# Driver-v1.net
KiCad netlist of a schematic drawn in EAGLE
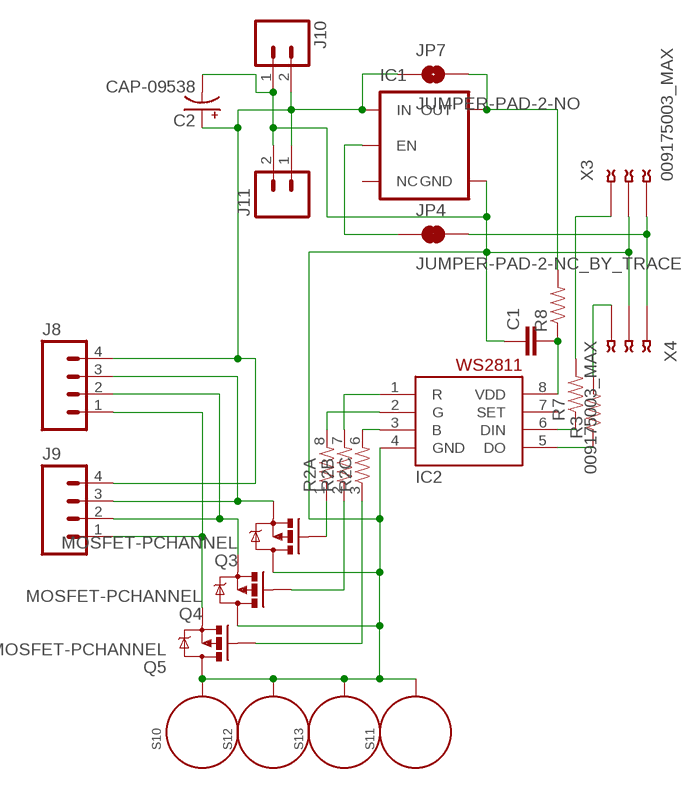
[diagram p0: schematic, sheet 1]

(export (version "E")
  (design (tool "Eeschema 10.0.6"))
  (components
    (comp (ref "C1")
      (value "CAP1206")
      (footprint "eagle-import:1206")
      (libsource (lib "eagle-import") (part "CAP1206"))
    )
    (comp (ref "C2")
      (value "CAP-09538")
      (footprint "eagle-import:CPOL-RADIAL-1000UF-25V")
      (libsource (lib "eagle-import") (part "1000UF-25V(PTH)"))
    )
    (comp (ref "IC1")
      (value "V_REG_TPS76433SOT23-5")
      (footprint "eagle-import:SOT23-5")
      (libsource (lib "eagle-import") (part "V_REG_TPS76433SOT23-5"))
    )
    (comp (ref "IC2")
      (value "WS2811-SOP8")
      (footprint "eagle-import:SO08-SKINNYPADS")
      (libsource (lib "eagle-import") (part "WS2811-SOP8"))
    )
    (comp (ref "J8")
      (value "M04LONGPADS")
      (footprint "eagle-import:1X04_LONGPADS")
      (libsource (lib "eagle-import") (part "M04LONGPADS"))
    )
    (comp (ref "J9")
      (value "M04LONGPADS")
      (footprint "eagle-import:1X04_LONGPADS")
      (libsource (lib "eagle-import") (part "M04LONGPADS"))
    )
    (comp (ref "J10")
      (value "M025MM")
      (footprint "eagle-import:SCREWTERMINAL-5MM-2")
      (libsource (lib "eagle-import") (part "M025MM"))
    )
    (comp (ref "J11")
      (value "M025MM")
      (footprint "eagle-import:SCREWTERMINAL-5MM-2")
      (libsource (lib "eagle-import") (part "M025MM"))
    )
    (comp (ref "JP4")
      (value "JUMPER-PAD-2-NC_BY_TRACE")
      (footprint "eagle-import:PAD-JUMPER-2-NC_BY_TRACE_YES_SILK")
      (libsource (lib "eagle-import") (part "JUMPER-PAD-2-NC_BY_TRACE"))
    )
    (comp (ref "JP7")
      (value "JUMPER-PAD-2-NO")
      (footprint "eagle-import:PAD-JUMPER-2-NO_NO_SILK")
      (libsource (lib "eagle-import") (part "JUMPER-PAD-2-NO"))
    )
    (comp (ref "Q3")
      (value "MOSFET-PCHANNEL")
      (footprint "eagle-import:SOT23-3")
      (libsource (lib "eagle-import") (part "MOSFET-PCHANNEL"))
    )
    (comp (ref "Q4")
      (value "MOSFET-PCHANNEL")
      (footprint "eagle-import:SOT23-3")
      (libsource (lib "eagle-import") (part "MOSFET-PCHANNEL"))
    )
    (comp (ref "Q5")
      (value "MOSFET-PCHANNEL")
      (footprint "eagle-import:SOT23-3")
      (libsource (lib "eagle-import") (part "MOSFET-PCHANNEL"))
    )
    (comp (ref "R2")
      (value "RESISTOR-ARRAY0603-ARV")
      (footprint "eagle-import:0603-ARV")
      (libsource (lib "eagle-import") (part "RESISTOR-ARRAY0603-ARV"))
    )
    (comp (ref "R3")
      (value "RESISTOR0603")
      (footprint "eagle-import:0603-RES")
      (libsource (lib "eagle-import") (part "RESISTOR0603"))
    )
    (comp (ref "R7")
      (value "RESISTOR0603")
      (footprint "eagle-import:0603-RES")
      (libsource (lib "eagle-import") (part "RESISTOR0603"))
    )
    (comp (ref "R8")
      (value "RESISTOR0805-RES")
      (footprint "eagle-import:0805")
      (libsource (lib "eagle-import") (part "RESISTOR0805-RES"))
    )
    (comp (ref "S10")
      (value "STANDOFF_ELECTRICAL")
      (footprint "eagle-import:STANDOFF-ELECTRICAL")
      (libsource (lib "eagle-import") (part "STANDOFF_ELECTRICAL"))
    )
    (comp (ref "S11")
      (value "STANDOFF_ELECTRICAL")
      (footprint "eagle-import:STANDOFF-ELECTRICAL")
      (libsource (lib "eagle-import") (part "STANDOFF_ELECTRICAL"))
    )
    (comp (ref "S12")
      (value "STANDOFF_ELECTRICAL")
      (footprint "eagle-import:STANDOFF-ELECTRICAL")
      (libsource (lib "eagle-import") (part "STANDOFF_ELECTRICAL"))
    )
    (comp (ref "S13")
      (value "STANDOFF_ELECTRICAL")
      (footprint "eagle-import:STANDOFF-ELECTRICAL")
      (libsource (lib "eagle-import") (part "STANDOFF_ELECTRICAL"))
    )
    (comp (ref "X3")
      (value "009175003_MAX")
      (footprint "eagle-import:009175003_MAX")
      (libsource (lib "eagle-import") (part "009175003_MAX"))
    )
    (comp (ref "X4")
      (value "009175003_MAX")
      (footprint "eagle-import:009175003_MAX")
      (libsource (lib "eagle-import") (part "009175003_MAX"))
    )
  )
  (nets
    (net (code "1") (name "Net-(IC1-EN)") (class "Default")
      (node (ref "IC1") (pin "3") (pinfunction "EN_3") (pintype "input"))
      (node (ref "JP4") (pin "1") (pinfunction "1_1") (pintype "passive"))
    )
    (net (code "2") (name "Net-(IC1-GND)") (class "Default")
      (node (ref "C1") (pin "1") (pinfunction "1_1") (pintype "passive"))
      (node (ref "C2") (pin "-") (pinfunction "-_-") (pintype "passive"))
      (node (ref "IC1") (pin "2") (pinfunction "GND_2") (pintype "input"))
      (node (ref "IC2") (pin "4") (pinfunction "GND_4") (pintype "power_in"))
      (node (ref "J10") (pin "1") (pinfunction "1_1") (pintype "passive"))
      (node (ref "J11") (pin "2") (pinfunction "2_2") (pintype "passive"))
      (node (ref "Q3") (pin "3") (pinfunction "D_3") (pintype "passive"))
      (node (ref "Q4") (pin "3") (pinfunction "D_3") (pintype "passive"))
      (node (ref "Q5") (pin "3") (pinfunction "D_3") (pintype "passive"))
      (node (ref "S10") (pin "P1") (pinfunction "P$1_P1") (pintype "bidirectional"))
      (node (ref "S11") (pin "P1") (pinfunction "P$1_P1") (pintype "bidirectional"))
      (node (ref "S12") (pin "P1") (pinfunction "P$1_P1") (pintype "bidirectional"))
      (node (ref "S13") (pin "P1") (pinfunction "P$1_P1") (pintype "bidirectional"))
      (node (ref "X3") (pin "2") (pinfunction "2_2") (pintype "passive"))
      (node (ref "X3") (pin "2@1") (pinfunction "2_2@1") (pintype "passive"))
      (node (ref "X4") (pin "2") (pinfunction "2_2") (pintype "passive"))
      (node (ref "X4") (pin "2@1") (pinfunction "2_2@1") (pintype "passive"))
    )
    (net (code "3") (name "Net-(IC1-IN)") (class "Default")
      (node (ref "C2") (pin "+") (pinfunction "+_+") (pintype "passive"))
      (node (ref "IC1") (pin "1") (pinfunction "IN_1") (pintype "input"))
      (node (ref "J10") (pin "2") (pinfunction "2_2") (pintype "passive"))
      (node (ref "J11") (pin "1") (pinfunction "1_1") (pintype "passive"))
      (node (ref "J8") (pin "4") (pinfunction "4_4") (pintype "passive"))
      (node (ref "J9") (pin "4") (pinfunction "4_4") (pintype "passive"))
      (node (ref "JP7") (pin "1") (pinfunction "1_1") (pintype "passive"))
    )
    (net (code "4") (name "Net-(IC1-OUT)") (class "Default")
      (node (ref "IC1") (pin "5") (pinfunction "OUT_5") (pintype "passive"))
      (node (ref "JP7") (pin "2") (pinfunction "2_2") (pintype "passive"))
      (node (ref "R8") (pin "2") (pinfunction "2_2") (pintype "passive"))
    )
    (net (code "5") (name "Net-(IC2-B)") (class "Default")
      (node (ref "IC2") (pin "3") (pinfunction "B_3") (pintype "open_collector"))
      (node (ref "R2") (pin "6") (pinfunction "2_6") (pintype "passive"))
    )
    (net (code "6") (name "Net-(IC2-DIN)") (class "Default")
      (node (ref "IC2") (pin "6") (pinfunction "DIN_6") (pintype "input"))
      (node (ref "R7") (pin "1") (pinfunction "1_1") (pintype "passive"))
    )
    (net (code "7") (name "Net-(IC2-DO)") (class "Default")
      (node (ref "IC2") (pin "5") (pinfunction "DO_5") (pintype "output"))
      (node (ref "R3") (pin "1") (pinfunction "1_1") (pintype "passive"))
    )
    (net (code "8") (name "Net-(IC2-G)") (class "Default")
      (node (ref "IC2") (pin "2") (pinfunction "G_2") (pintype "open_collector"))
      (node (ref "R2") (pin "8") (pinfunction "2_8") (pintype "passive"))
    )
    (net (code "9") (name "Net-(IC2-R)") (class "Default")
      (node (ref "IC2") (pin "1") (pinfunction "R_1") (pintype "open_collector"))
      (node (ref "R2") (pin "7") (pinfunction "2_7") (pintype "passive"))
    )
    (net (code "10") (name "Net-(IC2-VDD)") (class "Default")
      (node (ref "C1") (pin "2") (pinfunction "2_2") (pintype "passive"))
      (node (ref "IC2") (pin "8") (pinfunction "VDD_8") (pintype "power_in"))
      (node (ref "R8") (pin "1") (pinfunction "1_1") (pintype "passive"))
    )
    (net (code "11") (name "Net-(JP4-Pad2)") (class "Default")
      (node (ref "JP4") (pin "2") (pinfunction "2_2") (pintype "passive"))
      (node (ref "X3") (pin "3") (pinfunction "3_3") (pintype "passive"))
      (node (ref "X3") (pin "3@2") (pinfunction "3_3@2") (pintype "passive"))
      (node (ref "X4") (pin "1") (pinfunction "1_1") (pintype "passive"))
      (node (ref "X4") (pin "1@1") (pinfunction "1_1@1") (pintype "passive"))
    )
    (net (code "12") (name "Net-(Q3-G)") (class "Default")
      (node (ref "Q3") (pin "1") (pinfunction "G_1") (pintype "passive"))
      (node (ref "R2") (pin "1") (pinfunction "1_1") (pintype "passive"))
    )
    (net (code "13") (name "Net-(Q3-S)") (class "Default")
      (node (ref "J8") (pin "3") (pinfunction "3_3") (pintype "passive"))
      (node (ref "J9") (pin "3") (pinfunction "3_3") (pintype "passive"))
      (node (ref "Q3") (pin "2") (pinfunction "S_2") (pintype "passive"))
    )
    (net (code "14") (name "Net-(Q4-G)") (class "Default")
      (node (ref "Q4") (pin "1") (pinfunction "G_1") (pintype "passive"))
      (node (ref "R2") (pin "2") (pinfunction "1_2") (pintype "passive"))
    )
    (net (code "15") (name "Net-(Q4-S)") (class "Default")
      (node (ref "J8") (pin "2") (pinfunction "2_2") (pintype "passive"))
      (node (ref "J9") (pin "2") (pinfunction "2_2") (pintype "passive"))
      (node (ref "Q4") (pin "2") (pinfunction "S_2") (pintype "passive"))
    )
    (net (code "16") (name "Net-(Q5-G)") (class "Default")
      (node (ref "Q5") (pin "1") (pinfunction "G_1") (pintype "passive"))
      (node (ref "R2") (pin "3") (pinfunction "1_3") (pintype "passive"))
    )
    (net (code "17") (name "Net-(Q5-S)") (class "Default")
      (node (ref "J8") (pin "1") (pinfunction "1_1") (pintype "passive"))
      (node (ref "J9") (pin "1") (pinfunction "1_1") (pintype "passive"))
      (node (ref "Q5") (pin "2") (pinfunction "S_2") (pintype "passive"))
    )
    (net (code "18") (name "Net-(R3-Pad2)") (class "Default")
      (node (ref "R3") (pin "2") (pinfunction "2_2") (pintype "passive"))
      (node (ref "X4") (pin "3") (pinfunction "3_3") (pintype "passive"))
      (node (ref "X4") (pin "3@2") (pinfunction "3_3@2") (pintype "passive"))
    )
    (net (code "19") (name "Net-(R7-Pad2)") (class "Default")
      (node (ref "R7") (pin "2") (pinfunction "2_2") (pintype "passive"))
      (node (ref "X3") (pin "1") (pinfunction "1_1") (pintype "passive"))
      (node (ref "X3") (pin "1@1") (pinfunction "1_1@1") (pintype "passive"))
    )
    (net (code "20") (name "unconnected-(IC1-NC-Pad4)") (class "Default")
      (node (ref "IC1") (pin "4") (pinfunction "NC_4") (pintype "input"))
    )
    (net (code "21") (name "unconnected-(IC2-SET-Pad7)") (class "Default")
      (node (ref "IC2") (pin "7") (pinfunction "SET_7") (pintype "input"))
    )
  )
)
